# GALX4-0047N_PCB-1109N_REV-A_io_1.net
KiCad netlist of a schematic drawn in Altium Designer
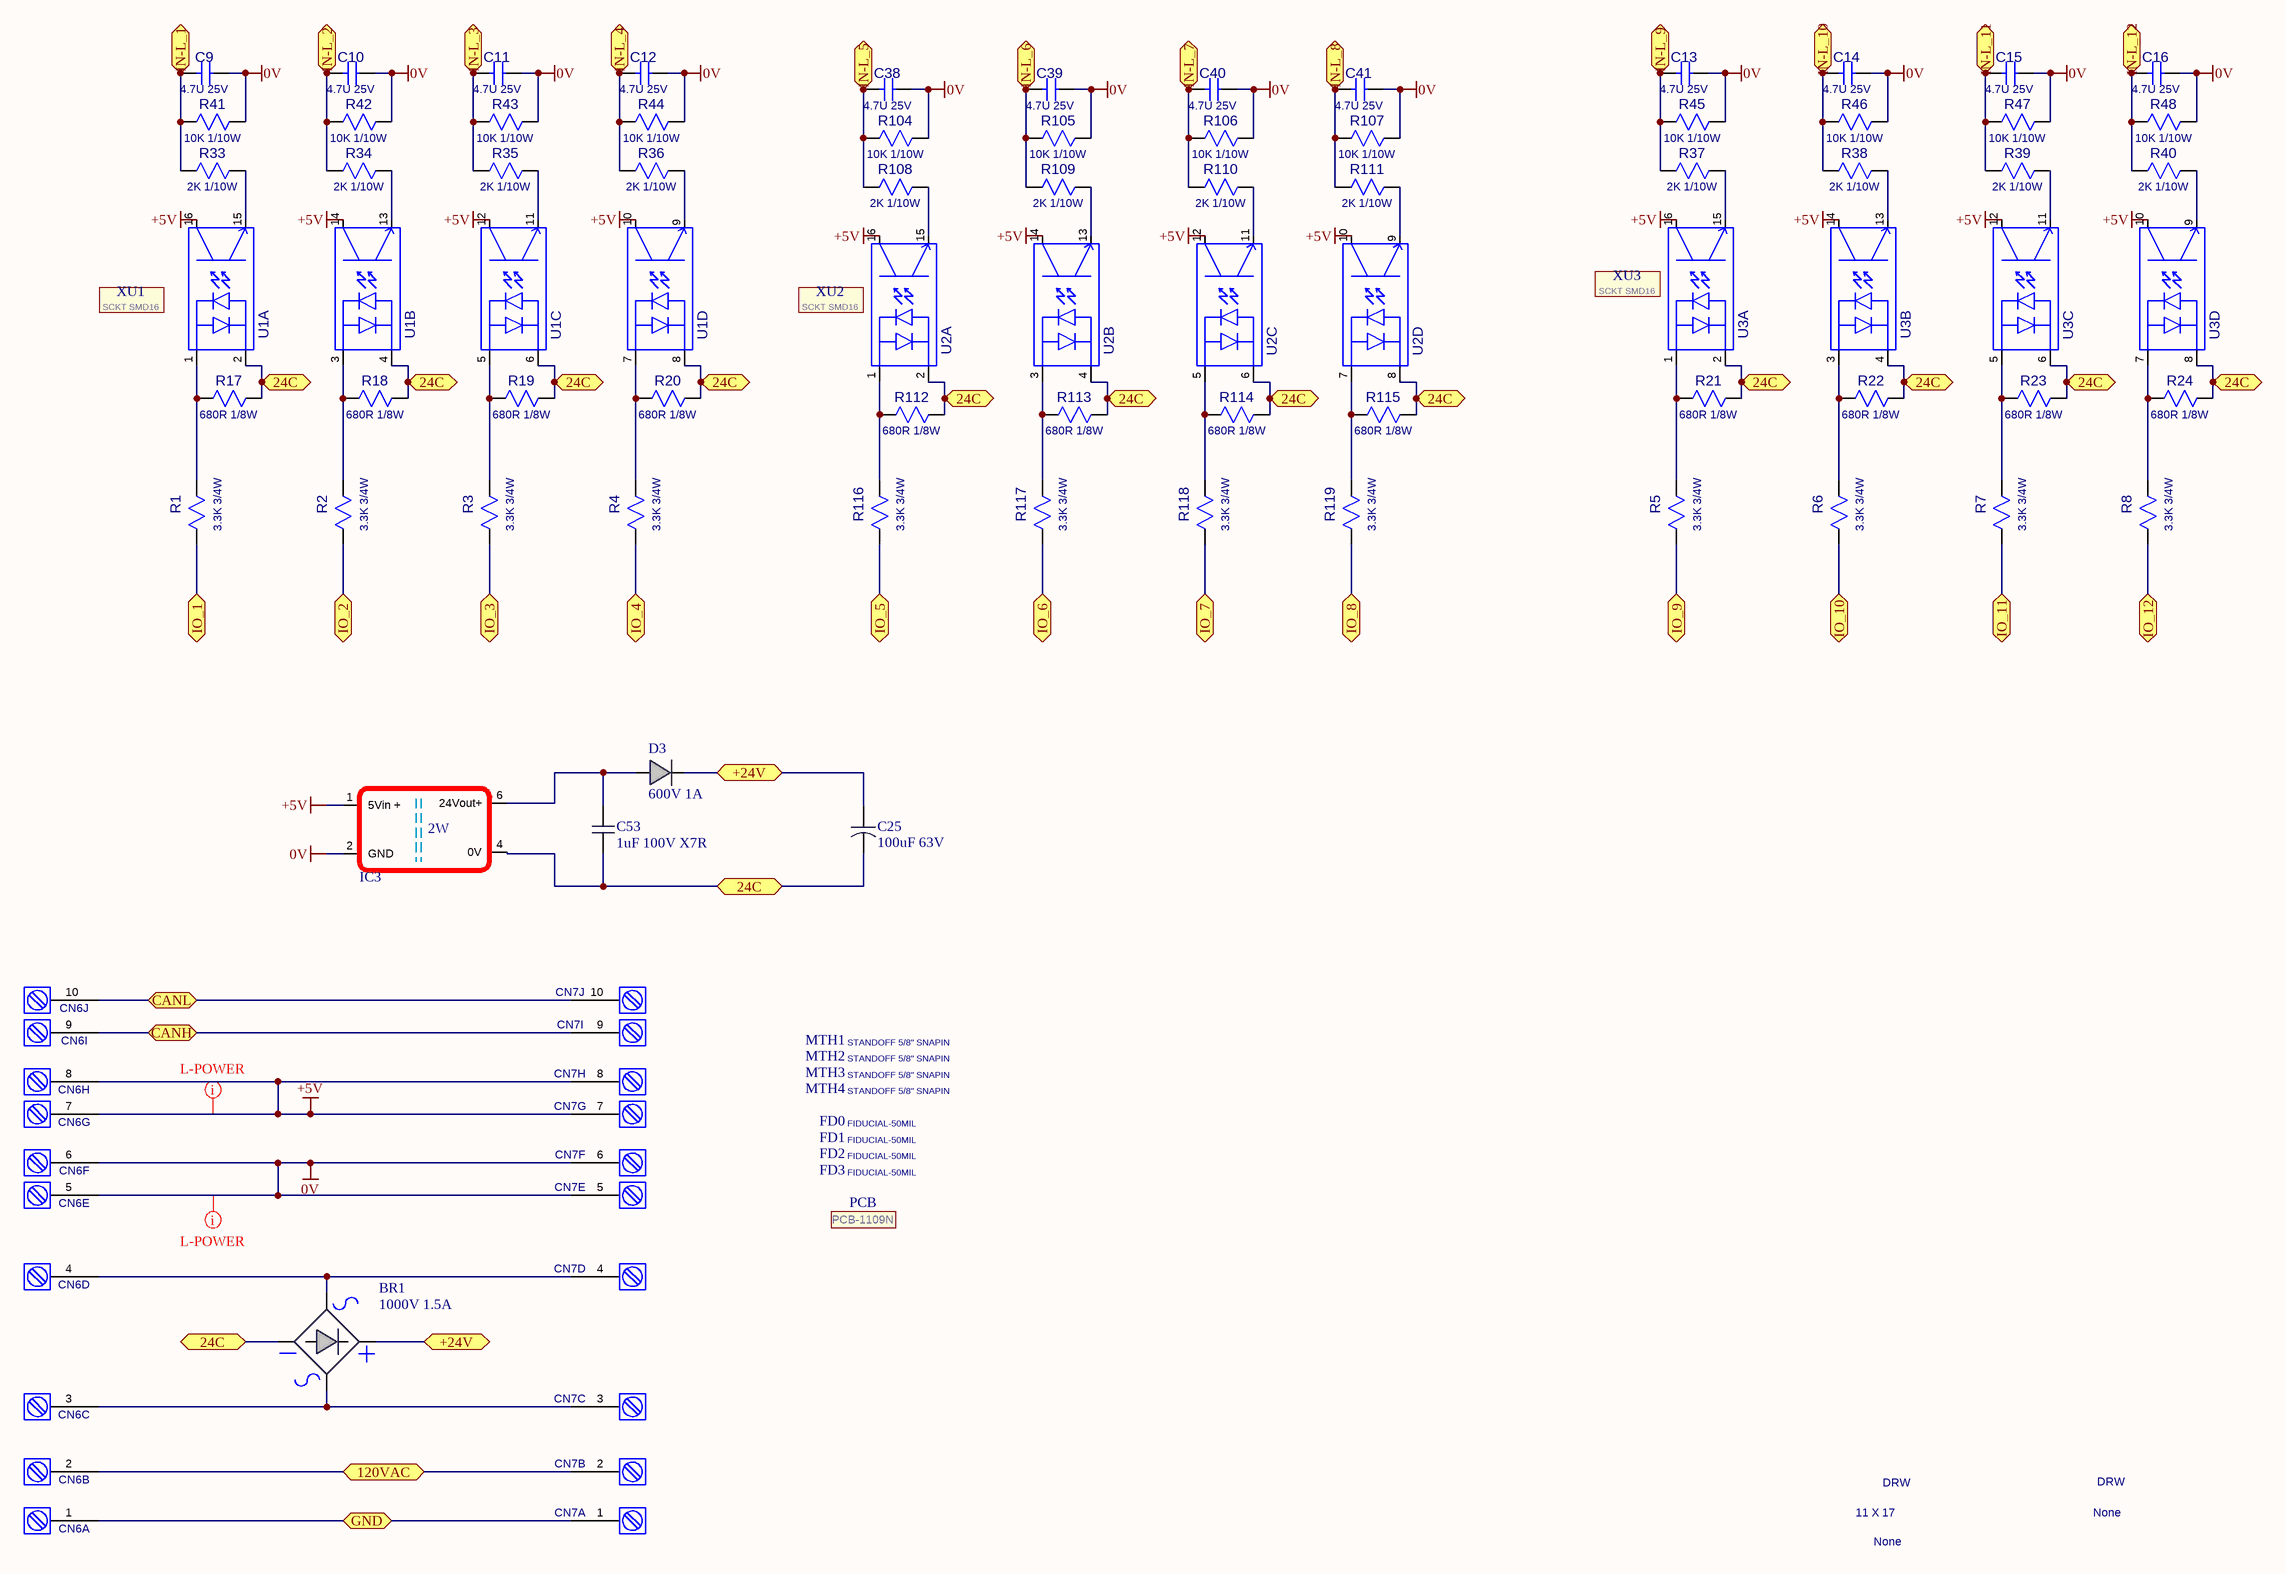
[diagram p0: GALX4-0047N_PCB-1109N_REV-A_io_1.SchDoc]

(export (version "E")
  (design (tool "Eeschema 10.0.6"))
  (components
    (comp (ref "BR1")
      (value "1000V 1.5A")
      (footprint "SDIP4")
      (description "DIODE,RECT BRIDGE 1000V 1.5A 4SDIP SMT")
      (fields (field (name "MANUFACTURER") "FAIRCHILD"))
      (libsource (lib "My Local Library") (part "DIOD-0081N"))
    )
    (comp (ref "C9")
      (value "4.7U 25V")
      (footprint "0805")
      (description "C-0805-D-4.7U-25V-10%")
      (fields (field (name "MANUFACTURER") "MURATA") (field (name "Comment") "CAP-0098N"))
      (libsource (lib "CAPACITOR") (part "CAP-0098N"))
    )
    (comp (ref "C10")
      (value "4.7U 25V")
      (footprint "0805")
      (description "C-0805-D-4.7U-25V-10%")
      (fields (field (name "MANUFACTURER") "MURATA") (field (name "Comment") "CAP-0098N"))
      (libsource (lib "CAPACITOR") (part "CAP-0098N"))
    )
    (comp (ref "C11")
      (value "4.7U 25V")
      (footprint "0805")
      (description "C-0805-D-4.7U-25V-10%")
      (fields (field (name "MANUFACTURER") "MURATA") (field (name "Comment") "CAP-0098N"))
      (libsource (lib "CAPACITOR") (part "CAP-0098N"))
    )
    (comp (ref "C12")
      (value "4.7U 25V")
      (footprint "0805")
      (description "C-0805-D-4.7U-25V-10%")
      (fields (field (name "MANUFACTURER") "MURATA") (field (name "Comment") "CAP-0098N"))
      (libsource (lib "CAPACITOR") (part "CAP-0098N"))
    )
    (comp (ref "C13")
      (value "4.7U 25V")
      (footprint "0805")
      (description "C-0805-D-4.7U-25V-10%")
      (fields (field (name "MANUFACTURER") "MURATA") (field (name "Comment") "CAP-0098N"))
      (libsource (lib "CAPACITOR") (part "CAP-0098N"))
    )
    (comp (ref "C14")
      (value "4.7U 25V")
      (footprint "0805")
      (description "C-0805-D-4.7U-25V-10%")
      (fields (field (name "MANUFACTURER") "MURATA") (field (name "Comment") "CAP-0098N"))
      (libsource (lib "CAPACITOR") (part "CAP-0098N"))
    )
    (comp (ref "C15")
      (value "4.7U 25V")
      (footprint "0805")
      (description "C-0805-D-4.7U-25V-10%")
      (fields (field (name "MANUFACTURER") "MURATA") (field (name "Comment") "CAP-0098N"))
      (libsource (lib "CAPACITOR") (part "CAP-0098N"))
    )
    (comp (ref "C16")
      (value "4.7U 25V")
      (footprint "0805")
      (description "C-0805-D-4.7U-25V-10%")
      (fields (field (name "MANUFACTURER") "MURATA") (field (name "Comment") "CAP-0098N"))
      (libsource (lib "CAPACITOR") (part "CAP-0098N"))
    )
    (comp (ref "C25")
      (value "100uF 63V")
      (footprint "D10.3")
      (description "CAP, 100UF 63V ELECT 20% 10.3MM SMT")
      (fields (field (name "MANUFACTURER") "UNITED CHEMICON"))
      (libsource (lib "My Local Library") (part "CAP-0104N"))
    )
    (comp (ref "C38")
      (value "4.7U 25V")
      (footprint "0805")
      (description "C-0805-D-4.7U-25V-10%")
      (fields (field (name "MANUFACTURER") "MURATA") (field (name "Comment") "CAP-0098N"))
      (libsource (lib "CAPACITOR") (part "CAP-0098N"))
    )
    (comp (ref "C39")
      (value "4.7U 25V")
      (footprint "0805")
      (description "C-0805-D-4.7U-25V-10%")
      (fields (field (name "MANUFACTURER") "MURATA") (field (name "Comment") "CAP-0098N"))
      (libsource (lib "CAPACITOR") (part "CAP-0098N"))
    )
    (comp (ref "C40")
      (value "4.7U 25V")
      (footprint "0805")
      (description "C-0805-D-4.7U-25V-10%")
      (fields (field (name "MANUFACTURER") "MURATA") (field (name "Comment") "CAP-0098N"))
      (libsource (lib "CAPACITOR") (part "CAP-0098N"))
    )
    (comp (ref "C41")
      (value "4.7U 25V")
      (footprint "0805")
      (description "C-0805-D-4.7U-25V-10%")
      (fields (field (name "MANUFACTURER") "MURATA") (field (name "Comment") "CAP-0098N"))
      (libsource (lib "CAPACITOR") (part "CAP-0098N"))
    )
    (comp (ref "C53")
      (value "1uF 100V X7R")
      (footprint "1206 - CAP")
      (description "CAP, 1UF 100V 10% X7R CERM 1206 SMT")
      (fields (field (name "MANUFACTURER") "MURATA"))
      (libsource (lib "My Local Library") (part "CAP-0110N"))
    )
    (comp (ref "CN6")
      (value "CONN-0193N")
      (footprint "CN_150_10P_VERT")
      (description "CN_150_10P_VERT")
      (fields (field (name "MANUFACTURER") "PHOENIX"))
      (libsource (lib "") (part "CONN-0193N_1"))
    )
    (comp (ref "CN7")
      (value "CONN-0193N")
      (footprint "CN_150_10P_VERT")
      (description "CN_150_10P_VERT")
      (fields (field (name "MANUFACTURER") "PHOENIX"))
      (libsource (lib "") (part "CONN-0193N_4"))
    )
    (comp (ref "D3")
      (value "600V 1A")
      (footprint "SMA")
      (description "DIODE,FAST 600V 1A SMA SMT")
      (fields (field (name "MANUFACTURER") "STMICRO"))
      (libsource (lib "My Local Library") (part "DIOD-0077N"))
    )
    (comp (ref "FD0")
      (value "FIDUCIAL-50MIL")
      (footprint "FIDUCIAL-50MIL")
      (libsource (lib "MISC") (part "FIDUCIAL-50MIL"))
    )
    (comp (ref "FD1")
      (value "FIDUCIAL-50MIL")
      (footprint "FIDUCIAL-50MIL")
      (libsource (lib "MISC") (part "FIDUCIAL-50MIL"))
    )
    (comp (ref "FD2")
      (value "FIDUCIAL-50MIL")
      (footprint "FIDUCIAL-50MIL")
      (libsource (lib "MISC") (part "FIDUCIAL-50MIL"))
    )
    (comp (ref "FD3")
      (value "FIDUCIAL-50MIL")
      (footprint "FIDUCIAL-50MIL")
      (libsource (lib "MISC") (part "FIDUCIAL-50MIL"))
    )
    (comp (ref "IC3")
      (value "PDM2-S5-S24-S")
      (footprint "PDM2-S5-S24-S")
      (description "CONV DC/DC 2W  5 --> 24V OUT SIP4")
      (fields (field (name "MANUFACTURER") "CUI INC"))
      (libsource (lib "My Local Library") (part "IC-PDM2-S5-S24-S"))
    )
    (comp (ref "MTH1")
      (value "STANDOFF 5/8\" SNAPIN")
      (footprint "STANDOFF-8-5/8\"")
      (description "STANDOFF-5/8-SNAP")
      (fields (field (name "MANUFACTURER") "KEYSTONE") (field (name "Comment") "HWPC-0018N"))
      (libsource (lib "MISC") (part "HWPC-0018N"))
    )
    (comp (ref "MTH2")
      (value "STANDOFF 5/8\" SNAPIN")
      (footprint "STANDOFF-8-5/8\"")
      (description "STANDOFF-5/8-SNAP")
      (fields (field (name "MANUFACTURER") "KEYSTONE") (field (name "Comment") "HWPC-0018N"))
      (libsource (lib "MISC") (part "HWPC-0018N"))
    )
    (comp (ref "MTH3")
      (value "STANDOFF 5/8\" SNAPIN")
      (footprint "STANDOFF-8-5/8\"")
      (description "STANDOFF-5/8-SNAP")
      (fields (field (name "MANUFACTURER") "KEYSTONE") (field (name "Comment") "HWPC-0018N"))
      (libsource (lib "MISC") (part "HWPC-0018N"))
    )
    (comp (ref "MTH4")
      (value "STANDOFF 5/8\" SNAPIN")
      (footprint "STANDOFF-8-5/8\"")
      (description "STANDOFF-5/8-SNAP")
      (fields (field (name "MANUFACTURER") "KEYSTONE") (field (name "Comment") "HWPC-0018N"))
      (libsource (lib "MISC") (part "HWPC-0018N"))
    )
    (comp (ref "PCB")
      (value "PCB")
      (description "PCB-0205N")
      (fields (field (name "MANUFACTURER") "CIRCUIT ENG") (field (name "GAL P/N") "PCB-1109N"))
      (libsource (lib "MISC") (part "PCB"))
    )
    (comp (ref "R1")
      (value "3.3K 3/4W")
      (footprint "2010")
      (description "R-2010-B-3.3K-3/4-5%")
      (fields (field (name "MANUFACTURER") "KOA SPEER") (field (name "Comment") "RES-0348N"))
      (libsource (lib "RESISTOR") (part "RES-0348N"))
    )
    (comp (ref "R2")
      (value "3.3K 3/4W")
      (footprint "2010")
      (description "R-2010-B-3.3K-3/4-5%")
      (fields (field (name "MANUFACTURER") "KOA SPEER") (field (name "Comment") "RES-0348N"))
      (libsource (lib "RESISTOR") (part "RES-0348N"))
    )
    (comp (ref "R3")
      (value "3.3K 3/4W")
      (footprint "2010")
      (description "R-2010-B-3.3K-3/4-5%")
      (fields (field (name "MANUFACTURER") "KOA SPEER") (field (name "Comment") "RES-0348N"))
      (libsource (lib "RESISTOR") (part "RES-0348N"))
    )
    (comp (ref "R4")
      (value "3.3K 3/4W")
      (footprint "2010")
      (description "R-2010-B-3.3K-3/4-5%")
      (fields (field (name "MANUFACTURER") "KOA SPEER") (field (name "Comment") "RES-0348N"))
      (libsource (lib "RESISTOR") (part "RES-0348N"))
    )
    (comp (ref "R5")
      (value "3.3K 3/4W")
      (footprint "2010")
      (description "R-2010-B-3.3K-3/4-5%")
      (fields (field (name "MANUFACTURER") "KOA SPEER") (field (name "Comment") "RES-0348N"))
      (libsource (lib "RESISTOR") (part "RES-0348N"))
    )
    (comp (ref "R6")
      (value "3.3K 3/4W")
      (footprint "2010")
      (description "R-2010-B-3.3K-3/4-5%")
      (fields (field (name "MANUFACTURER") "KOA SPEER") (field (name "Comment") "RES-0348N"))
      (libsource (lib "RESISTOR") (part "RES-0348N"))
    )
    (comp (ref "R7")
      (value "3.3K 3/4W")
      (footprint "2010")
      (description "R-2010-B-3.3K-3/4-5%")
      (fields (field (name "MANUFACTURER") "KOA SPEER") (field (name "Comment") "RES-0348N"))
      (libsource (lib "RESISTOR") (part "RES-0348N"))
    )
    (comp (ref "R8")
      (value "3.3K 3/4W")
      (footprint "2010")
      (description "R-2010-B-3.3K-3/4-5%")
      (fields (field (name "MANUFACTURER") "KOA SPEER") (field (name "Comment") "RES-0348N"))
      (libsource (lib "RESISTOR") (part "RES-0348N"))
    )
    (comp (ref "R17")
      (value "680R 1/8W")
      (footprint "0805")
      (description "R-0805-A-680R-1/8-5%")
      (fields (field (name "MANUFACTURER") "YAGEO") (field (name "Comment") "RES-0338N"))
      (libsource (lib "RESISTOR") (part "RES-0338N"))
    )
    (comp (ref "R18")
      (value "680R 1/8W")
      (footprint "0805")
      (description "R-0805-A-680R-1/8-5%")
      (fields (field (name "MANUFACTURER") "YAGEO") (field (name "Comment") "RES-0338N"))
      (libsource (lib "RESISTOR") (part "RES-0338N"))
    )
    (comp (ref "R19")
      (value "680R 1/8W")
      (footprint "0805")
      (description "R-0805-A-680R-1/8-5%")
      (fields (field (name "MANUFACTURER") "YAGEO") (field (name "Comment") "RES-0338N"))
      (libsource (lib "RESISTOR") (part "RES-0338N"))
    )
    (comp (ref "R20")
      (value "680R 1/8W")
      (footprint "0805")
      (description "R-0805-A-680R-1/8-5%")
      (fields (field (name "MANUFACTURER") "YAGEO") (field (name "Comment") "RES-0338N"))
      (libsource (lib "RESISTOR") (part "RES-0338N"))
    )
    (comp (ref "R21")
      (value "680R 1/8W")
      (footprint "0805")
      (description "R-0805-A-680R-1/8-5%")
      (fields (field (name "MANUFACTURER") "YAGEO") (field (name "Comment") "RES-0338N"))
      (libsource (lib "RESISTOR") (part "RES-0338N"))
    )
    (comp (ref "R22")
      (value "680R 1/8W")
      (footprint "0805")
      (description "R-0805-A-680R-1/8-5%")
      (fields (field (name "MANUFACTURER") "YAGEO") (field (name "Comment") "RES-0338N"))
      (libsource (lib "RESISTOR") (part "RES-0338N"))
    )
    (comp (ref "R23")
      (value "680R 1/8W")
      (footprint "0805")
      (description "R-0805-A-680R-1/8-5%")
      (fields (field (name "MANUFACTURER") "YAGEO") (field (name "Comment") "RES-0338N"))
      (libsource (lib "RESISTOR") (part "RES-0338N"))
    )
    (comp (ref "R24")
      (value "680R 1/8W")
      (footprint "0805")
      (description "R-0805-A-680R-1/8-5%")
      (fields (field (name "MANUFACTURER") "YAGEO") (field (name "Comment") "RES-0338N"))
      (libsource (lib "RESISTOR") (part "RES-0338N"))
    )
    (comp (ref "R33")
      (value "2K 1/10W")
      (footprint "0603")
      (description "R-0603-B-2.0K-1/10-5%")
      (fields (field (name "MANUFACTURER") "PANASONIC-ECG") (field (name "Comment") "RES-0315N"))
      (libsource (lib "RESISTOR") (part "RES-0315N"))
    )
    (comp (ref "R34")
      (value "2K 1/10W")
      (footprint "0603")
      (description "R-0603-B-2.0K-1/10-5%")
      (fields (field (name "MANUFACTURER") "PANASONIC-ECG") (field (name "Comment") "RES-0315N"))
      (libsource (lib "RESISTOR") (part "RES-0315N"))
    )
    (comp (ref "R35")
      (value "2K 1/10W")
      (footprint "0603")
      (description "R-0603-B-2.0K-1/10-5%")
      (fields (field (name "MANUFACTURER") "PANASONIC-ECG") (field (name "Comment") "RES-0315N"))
      (libsource (lib "RESISTOR") (part "RES-0315N"))
    )
    (comp (ref "R36")
      (value "2K 1/10W")
      (footprint "0603")
      (description "R-0603-B-2.0K-1/10-5%")
      (fields (field (name "MANUFACTURER") "PANASONIC-ECG") (field (name "Comment") "RES-0315N"))
      (libsource (lib "RESISTOR") (part "RES-0315N"))
    )
    (comp (ref "R37")
      (value "2K 1/10W")
      (footprint "0603")
      (description "R-0603-B-2.0K-1/10-5%")
      (fields (field (name "MANUFACTURER") "PANASONIC-ECG") (field (name "Comment") "RES-0315N"))
      (libsource (lib "RESISTOR") (part "RES-0315N"))
    )
    (comp (ref "R38")
      (value "2K 1/10W")
      (footprint "0603")
      (description "R-0603-B-2.0K-1/10-5%")
      (fields (field (name "MANUFACTURER") "PANASONIC-ECG") (field (name "Comment") "RES-0315N"))
      (libsource (lib "RESISTOR") (part "RES-0315N"))
    )
    (comp (ref "R39")
      (value "2K 1/10W")
      (footprint "0603")
      (description "R-0603-B-2.0K-1/10-5%")
      (fields (field (name "MANUFACTURER") "PANASONIC-ECG") (field (name "Comment") "RES-0315N"))
      (libsource (lib "RESISTOR") (part "RES-0315N"))
    )
    (comp (ref "R40")
      (value "2K 1/10W")
      (footprint "0603")
      (description "R-0603-B-2.0K-1/10-5%")
      (fields (field (name "MANUFACTURER") "PANASONIC-ECG") (field (name "Comment") "RES-0315N"))
      (libsource (lib "RESISTOR") (part "RES-0315N"))
    )
    (comp (ref "R41")
      (value "10K 1/10W")
      (footprint "0603")
      (description "R-0603-B-10.0K-1/10-5%")
      (fields (field (name "MANUFACTURER") "PANASONIC-ECG") (field (name "Comment") "RES-0314N"))
      (libsource (lib "RESISTOR") (part "RES-0314N"))
    )
    (comp (ref "R42")
      (value "10K 1/10W")
      (footprint "0603")
      (description "R-0603-B-10.0K-1/10-5%")
      (fields (field (name "MANUFACTURER") "PANASONIC-ECG") (field (name "Comment") "RES-0314N"))
      (libsource (lib "RESISTOR") (part "RES-0314N"))
    )
    (comp (ref "R43")
      (value "10K 1/10W")
      (footprint "0603")
      (description "R-0603-B-10.0K-1/10-5%")
      (fields (field (name "MANUFACTURER") "PANASONIC-ECG") (field (name "Comment") "RES-0314N"))
      (libsource (lib "RESISTOR") (part "RES-0314N"))
    )
    (comp (ref "R44")
      (value "10K 1/10W")
      (footprint "0603")
      (description "R-0603-B-10.0K-1/10-5%")
      (fields (field (name "MANUFACTURER") "PANASONIC-ECG") (field (name "Comment") "RES-0314N"))
      (libsource (lib "RESISTOR") (part "RES-0314N"))
    )
    (comp (ref "R45")
      (value "10K 1/10W")
      (footprint "0603")
      (description "R-0603-B-10.0K-1/10-5%")
      (fields (field (name "MANUFACTURER") "PANASONIC-ECG") (field (name "Comment") "RES-0314N"))
      (libsource (lib "RESISTOR") (part "RES-0314N"))
    )
    (comp (ref "R46")
      (value "10K 1/10W")
      (footprint "0603")
      (description "R-0603-B-10.0K-1/10-5%")
      (fields (field (name "MANUFACTURER") "PANASONIC-ECG") (field (name "Comment") "RES-0314N"))
      (libsource (lib "RESISTOR") (part "RES-0314N"))
    )
    (comp (ref "R47")
      (value "10K 1/10W")
      (footprint "0603")
      (description "R-0603-B-10.0K-1/10-5%")
      (fields (field (name "MANUFACTURER") "PANASONIC-ECG") (field (name "Comment") "RES-0314N"))
      (libsource (lib "RESISTOR") (part "RES-0314N"))
    )
    (comp (ref "R48")
      (value "10K 1/10W")
      (footprint "0603")
      (description "R-0603-B-10.0K-1/10-5%")
      (fields (field (name "MANUFACTURER") "PANASONIC-ECG") (field (name "Comment") "RES-0314N"))
      (libsource (lib "RESISTOR") (part "RES-0314N"))
    )
    (comp (ref "R104")
      (value "10K 1/10W")
      (footprint "0603")
      (description "R-0603-B-10.0K-1/10-5%")
      (fields (field (name "MANUFACTURER") "PANASONIC-ECG") (field (name "Comment") "RES-0314N"))
      (libsource (lib "RESISTOR") (part "RES-0314N"))
    )
    (comp (ref "R105")
      (value "10K 1/10W")
      (footprint "0603")
      (description "R-0603-B-10.0K-1/10-5%")
      (fields (field (name "MANUFACTURER") "PANASONIC-ECG") (field (name "Comment") "RES-0314N"))
      (libsource (lib "RESISTOR") (part "RES-0314N"))
    )
    (comp (ref "R106")
      (value "10K 1/10W")
      (footprint "0603")
      (description "R-0603-B-10.0K-1/10-5%")
      (fields (field (name "MANUFACTURER") "PANASONIC-ECG") (field (name "Comment") "RES-0314N"))
      (libsource (lib "RESISTOR") (part "RES-0314N"))
    )
    (comp (ref "R107")
      (value "10K 1/10W")
      (footprint "0603")
      (description "R-0603-B-10.0K-1/10-5%")
      (fields (field (name "MANUFACTURER") "PANASONIC-ECG") (field (name "Comment") "RES-0314N"))
      (libsource (lib "RESISTOR") (part "RES-0314N"))
    )
    (comp (ref "R108")
      (value "2K 1/10W")
      (footprint "0603")
      (description "R-0603-B-2.0K-1/10-5%")
      (fields (field (name "MANUFACTURER") "PANASONIC-ECG") (field (name "Comment") "RES-0315N"))
      (libsource (lib "RESISTOR") (part "RES-0315N"))
    )
    (comp (ref "R109")
      (value "2K 1/10W")
      (footprint "0603")
      (description "R-0603-B-2.0K-1/10-5%")
      (fields (field (name "MANUFACTURER") "PANASONIC-ECG") (field (name "Comment") "RES-0315N"))
      (libsource (lib "RESISTOR") (part "RES-0315N"))
    )
    (comp (ref "R110")
      (value "2K 1/10W")
      (footprint "0603")
      (description "R-0603-B-2.0K-1/10-5%")
      (fields (field (name "MANUFACTURER") "PANASONIC-ECG") (field (name "Comment") "RES-0315N"))
      (libsource (lib "RESISTOR") (part "RES-0315N"))
    )
    (comp (ref "R111")
      (value "2K 1/10W")
      (footprint "0603")
      (description "R-0603-B-2.0K-1/10-5%")
      (fields (field (name "MANUFACTURER") "PANASONIC-ECG") (field (name "Comment") "RES-0315N"))
      (libsource (lib "RESISTOR") (part "RES-0315N"))
    )
    (comp (ref "R112")
      (value "680R 1/8W")
      (footprint "0805")
      (description "R-0805-A-680R-1/8-5%")
      (fields (field (name "MANUFACTURER") "YAGEO") (field (name "Comment") "RES-0338N"))
      (libsource (lib "RESISTOR") (part "RES-0338N"))
    )
    (comp (ref "R113")
      (value "680R 1/8W")
      (footprint "0805")
      (description "R-0805-A-680R-1/8-5%")
      (fields (field (name "MANUFACTURER") "YAGEO") (field (name "Comment") "RES-0338N"))
      (libsource (lib "RESISTOR") (part "RES-0338N"))
    )
    (comp (ref "R114")
      (value "680R 1/8W")
      (footprint "0805")
      (description "R-0805-A-680R-1/8-5%")
      (fields (field (name "MANUFACTURER") "YAGEO") (field (name "Comment") "RES-0338N"))
      (libsource (lib "RESISTOR") (part "RES-0338N"))
    )
    (comp (ref "R115")
      (value "680R 1/8W")
      (footprint "0805")
      (description "R-0805-A-680R-1/8-5%")
      (fields (field (name "MANUFACTURER") "YAGEO") (field (name "Comment") "RES-0338N"))
      (libsource (lib "RESISTOR") (part "RES-0338N"))
    )
    (comp (ref "R116")
      (value "3.3K 3/4W")
      (footprint "2010")
      (description "R-2010-B-3.3K-3/4-5%")
      (fields (field (name "MANUFACTURER") "KOA SPEER") (field (name "Comment") "RES-0348N"))
      (libsource (lib "RESISTOR") (part "RES-0348N"))
    )
    (comp (ref "R117")
      (value "3.3K 3/4W")
      (footprint "2010")
      (description "R-2010-B-3.3K-3/4-5%")
      (fields (field (name "MANUFACTURER") "KOA SPEER") (field (name "Comment") "RES-0348N"))
      (libsource (lib "RESISTOR") (part "RES-0348N"))
    )
    (comp (ref "R118")
      (value "3.3K 3/4W")
      (footprint "2010")
      (description "R-2010-B-3.3K-3/4-5%")
      (fields (field (name "MANUFACTURER") "KOA SPEER") (field (name "Comment") "RES-0348N"))
      (libsource (lib "RESISTOR") (part "RES-0348N"))
    )
    (comp (ref "R119")
      (value "3.3K 3/4W")
      (footprint "2010")
      (description "R-2010-B-3.3K-3/4-5%")
      (fields (field (name "MANUFACTURER") "KOA SPEER") (field (name "Comment") "RES-0348N"))
      (libsource (lib "RESISTOR") (part "RES-0348N"))
    )
    (comp (ref "U1")
      (value "IC-0068N")
      (footprint "DIP16FORSMD")
      (description "LTV-844-DIP16")
      (fields (field (name "MANUFACTURER") "LITE-ON"))
      (libsource (lib "IC") (part "IC-0068N"))
    )
    (comp (ref "U2")
      (value "IC-0068N")
      (footprint "DIP16FORSMD")
      (description "LTV-844-DIP16")
      (fields (field (name "MANUFACTURER") "LITE-ON"))
      (libsource (lib "IC") (part "IC-0068N"))
    )
    (comp (ref "U3")
      (value "IC-0068N")
      (footprint "DIP16FORSMD")
      (description "LTV-844-DIP16")
      (fields (field (name "MANUFACTURER") "LITE-ON"))
      (libsource (lib "IC") (part "IC-0068N"))
    )
    (comp (ref "XU1")
      (value "SCKT SMD16")
      (footprint "SCKT-SMD16")
      (description "SOCKET_SMD16")
      (fields (field (name "MANUFACTURER") "MILL-MAX") (field (name "Comment") "SCKT-0029N"))
      (libsource (lib "IC") (part "SCKT-0029N"))
    )
    (comp (ref "XU2")
      (value "SCKT SMD16")
      (footprint "SCKT-SMD16")
      (description "SOCKET_SMD16")
      (fields (field (name "MANUFACTURER") "MILL-MAX") (field (name "Comment") "SCKT-0029N"))
      (libsource (lib "IC") (part "SCKT-0029N"))
    )
    (comp (ref "XU3")
      (value "SCKT SMD16")
      (footprint "SCKT-SMD16")
      (description "SOCKET_SMD16")
      (fields (field (name "MANUFACTURER") "MILL-MAX") (field (name "Comment") "SCKT-0029N"))
      (libsource (lib "IC") (part "SCKT-0029N"))
    )
  )
  (nets
    (net (code "1") (name "+5V") (class "Default")
      (node (ref "CN6") (pin "7") (pintype "passive"))
      (node (ref "CN6") (pin "8") (pintype "passive"))
      (node (ref "CN7") (pin "7") (pintype "passive"))
      (node (ref "CN7") (pin "8") (pintype "passive"))
      (node (ref "IC3") (pin "1") (pinfunction "5Vin_+_1") (pintype "power_in"))
      (node (ref "U1") (pin "10") (pintype "passive"))
      (node (ref "U1") (pin "12") (pintype "passive"))
      (node (ref "U1") (pin "14") (pintype "passive"))
      (node (ref "U1") (pin "16") (pintype "passive"))
      (node (ref "U2") (pin "10") (pintype "passive"))
      (node (ref "U2") (pin "12") (pintype "passive"))
      (node (ref "U2") (pin "14") (pintype "passive"))
      (node (ref "U2") (pin "16") (pintype "passive"))
      (node (ref "U3") (pin "10") (pintype "passive"))
      (node (ref "U3") (pin "12") (pintype "passive"))
      (node (ref "U3") (pin "14") (pintype "passive"))
      (node (ref "U3") (pin "16") (pintype "passive"))
    )
    (net (code "2") (name "/+24V") (class "Default")
      (node (ref "BR1") (pin "1") (pinfunction "+_1") (pintype "passive"))
      (node (ref "C25") (pin "1") (pintype "passive"))
      (node (ref "D3") (pin "2") (pintype "passive"))
    )
    (net (code "3") (name "/24C") (class "Default")
      (node (ref "BR1") (pin "2") (pinfunction "-_2") (pintype "passive"))
      (node (ref "C25") (pin "2") (pintype "passive"))
      (node (ref "C53") (pin "1") (pinfunction "A_1") (pintype "passive"))
      (node (ref "IC3") (pin "4") (pinfunction "0V_4") (pintype "power_in"))
      (node (ref "R112") (pin "2") (pintype "passive"))
      (node (ref "R113") (pin "2") (pintype "passive"))
      (node (ref "R114") (pin "2") (pintype "passive"))
      (node (ref "R115") (pin "2") (pintype "passive"))
      (node (ref "R17") (pin "2") (pintype "passive"))
      (node (ref "R18") (pin "2") (pintype "passive"))
      (node (ref "R19") (pin "2") (pintype "passive"))
      (node (ref "R20") (pin "2") (pintype "passive"))
      (node (ref "R21") (pin "2") (pintype "passive"))
      (node (ref "R22") (pin "2") (pintype "passive"))
      (node (ref "R23") (pin "2") (pintype "passive"))
      (node (ref "R24") (pin "2") (pintype "passive"))
      (node (ref "U1") (pin "2") (pintype "passive"))
      (node (ref "U1") (pin "4") (pintype "passive"))
      (node (ref "U1") (pin "6") (pintype "passive"))
      (node (ref "U1") (pin "8") (pintype "passive"))
      (node (ref "U2") (pin "2") (pintype "passive"))
      (node (ref "U2") (pin "4") (pintype "passive"))
      (node (ref "U2") (pin "6") (pintype "passive"))
      (node (ref "U2") (pin "8") (pintype "passive"))
      (node (ref "U3") (pin "2") (pintype "passive"))
      (node (ref "U3") (pin "4") (pintype "passive"))
      (node (ref "U3") (pin "6") (pintype "passive"))
      (node (ref "U3") (pin "8") (pintype "passive"))
    )
    (net (code "4") (name "/120VAC") (class "Default")
      (node (ref "CN6") (pin "2") (pintype "passive"))
      (node (ref "CN7") (pin "2") (pintype "passive"))
    )
    (net (code "5") (name "/CANH") (class "Default")
      (node (ref "CN6") (pin "9") (pintype "passive"))
      (node (ref "CN7") (pin "9") (pintype "passive"))
    )
    (net (code "6") (name "/CANL") (class "Default")
      (node (ref "CN6") (pin "10") (pintype "passive"))
      (node (ref "CN7") (pin "10") (pintype "passive"))
    )
    (net (code "7") (name "/GND") (class "Default")
      (node (ref "CN6") (pin "1") (pintype "passive"))
      (node (ref "CN7") (pin "1") (pintype "passive"))
    )
    (net (code "8") (name "/IN-L_1") (class "Default")
      (node (ref "C9") (pin "1") (pinfunction "A_1") (pintype "passive"))
      (node (ref "R33") (pin "1") (pintype "passive"))
      (node (ref "R41") (pin "1") (pintype "passive"))
    )
    (net (code "9") (name "/IN-L_2") (class "Default")
      (node (ref "C10") (pin "1") (pinfunction "A_1") (pintype "passive"))
      (node (ref "R34") (pin "1") (pintype "passive"))
      (node (ref "R42") (pin "1") (pintype "passive"))
    )
    (net (code "10") (name "/IN-L_3") (class "Default")
      (node (ref "C11") (pin "1") (pinfunction "A_1") (pintype "passive"))
      (node (ref "R35") (pin "1") (pintype "passive"))
      (node (ref "R43") (pin "1") (pintype "passive"))
    )
    (net (code "11") (name "/IN-L_4") (class "Default")
      (node (ref "C12") (pin "1") (pinfunction "A_1") (pintype "passive"))
      (node (ref "R36") (pin "1") (pintype "passive"))
      (node (ref "R44") (pin "1") (pintype "passive"))
    )
    (net (code "12") (name "/IN-L_5") (class "Default")
      (node (ref "C38") (pin "1") (pinfunction "A_1") (pintype "passive"))
      (node (ref "R104") (pin "1") (pintype "passive"))
      (node (ref "R108") (pin "1") (pintype "passive"))
    )
    (net (code "13") (name "/IN-L_6") (class "Default")
      (node (ref "C39") (pin "1") (pinfunction "A_1") (pintype "passive"))
      (node (ref "R105") (pin "1") (pintype "passive"))
      (node (ref "R109") (pin "1") (pintype "passive"))
    )
    (net (code "14") (name "/IN-L_7") (class "Default")
      (node (ref "C40") (pin "1") (pinfunction "A_1") (pintype "passive"))
      (node (ref "R106") (pin "1") (pintype "passive"))
      (node (ref "R110") (pin "1") (pintype "passive"))
    )
    (net (code "15") (name "/IN-L_8") (class "Default")
      (node (ref "C41") (pin "1") (pinfunction "A_1") (pintype "passive"))
      (node (ref "R107") (pin "1") (pintype "passive"))
      (node (ref "R111") (pin "1") (pintype "passive"))
    )
    (net (code "16") (name "/IN-L_9") (class "Default")
      (node (ref "C13") (pin "1") (pinfunction "A_1") (pintype "passive"))
      (node (ref "R37") (pin "1") (pintype "passive"))
      (node (ref "R45") (pin "1") (pintype "passive"))
    )
    (net (code "17") (name "/IN-L_10") (class "Default")
      (node (ref "C14") (pin "1") (pinfunction "A_1") (pintype "passive"))
      (node (ref "R38") (pin "1") (pintype "passive"))
      (node (ref "R46") (pin "1") (pintype "passive"))
    )
    (net (code "18") (name "/IN-L_11") (class "Default")
      (node (ref "C15") (pin "1") (pinfunction "A_1") (pintype "passive"))
      (node (ref "R39") (pin "1") (pintype "passive"))
      (node (ref "R47") (pin "1") (pintype "passive"))
    )
    (net (code "19") (name "/IN-L_12") (class "Default")
      (node (ref "C16") (pin "1") (pinfunction "A_1") (pintype "passive"))
      (node (ref "R40") (pin "1") (pintype "passive"))
      (node (ref "R48") (pin "1") (pintype "passive"))
    )
    (net (code "20") (name "/IO_1") (class "Default") (node (ref "R1") (pin "1") (pintype "passive")))
    (net (code "21") (name "/IO_2") (class "Default") (node (ref "R2") (pin "1") (pintype "passive")))
    (net (code "22") (name "/IO_3") (class "Default") (node (ref "R3") (pin "1") (pintype "passive")))
    (net (code "23") (name "/IO_4") (class "Default") (node (ref "R4") (pin "1") (pintype "passive")))
    (net (code "24") (name "/IO_5") (class "Default") (node (ref "R116") (pin "1") (pintype "passive")))
    (net (code "25") (name "/IO_6") (class "Default") (node (ref "R117") (pin "1") (pintype "passive")))
    (net (code "26") (name "/IO_7") (class "Default") (node (ref "R118") (pin "1") (pintype "passive")))
    (net (code "27") (name "/IO_8") (class "Default") (node (ref "R119") (pin "1") (pintype "passive")))
    (net (code "28") (name "/IO_9") (class "Default") (node (ref "R5") (pin "1") (pintype "passive")))
    (net (code "29") (name "/IO_10") (class "Default") (node (ref "R6") (pin "1") (pintype "passive")))
    (net (code "30") (name "/IO_11") (class "Default") (node (ref "R7") (pin "1") (pintype "passive")))
    (net (code "31") (name "/IO_12") (class "Default") (node (ref "R8") (pin "1") (pintype "passive")))
    (net (code "32") (name "0V") (class "Default")
      (node (ref "C10") (pin "2") (pinfunction "B_2") (pintype "passive"))
      (node (ref "C11") (pin "2") (pinfunction "B_2") (pintype "passive"))
      (node (ref "C12") (pin "2") (pinfunction "B_2") (pintype "passive"))
      (node (ref "C13") (pin "2") (pinfunction "B_2") (pintype "passive"))
      (node (ref "C14") (pin "2") (pinfunction "B_2") (pintype "passive"))
      (node (ref "C15") (pin "2") (pinfunction "B_2") (pintype "passive"))
      (node (ref "C16") (pin "2") (pinfunction "B_2") (pintype "passive"))
      (node (ref "C38") (pin "2") (pinfunction "B_2") (pintype "passive"))
      (node (ref "C39") (pin "2") (pinfunction "B_2") (pintype "passive"))
      (node (ref "C40") (pin "2") (pinfunction "B_2") (pintype "passive"))
      (node (ref "C41") (pin "2") (pinfunction "B_2") (pintype "passive"))
      (node (ref "C9") (pin "2") (pinfunction "B_2") (pintype "passive"))
      (node (ref "CN6") (pin "5") (pintype "passive"))
      (node (ref "CN6") (pin "6") (pintype "passive"))
      (node (ref "CN7") (pin "5") (pintype "passive"))
      (node (ref "CN7") (pin "6") (pintype "passive"))
      (node (ref "IC3") (pin "2") (pinfunction "GND_2") (pintype "power_in"))
      (node (ref "R104") (pin "2") (pintype "passive"))
      (node (ref "R105") (pin "2") (pintype "passive"))
      (node (ref "R106") (pin "2") (pintype "passive"))
      (node (ref "R107") (pin "2") (pintype "passive"))
      (node (ref "R41") (pin "2") (pintype "passive"))
      (node (ref "R42") (pin "2") (pintype "passive"))
      (node (ref "R43") (pin "2") (pintype "passive"))
      (node (ref "R44") (pin "2") (pintype "passive"))
      (node (ref "R45") (pin "2") (pintype "passive"))
      (node (ref "R46") (pin "2") (pintype "passive"))
      (node (ref "R47") (pin "2") (pintype "passive"))
      (node (ref "R48") (pin "2") (pintype "passive"))
    )
    (net (code "33") (name "Net-(BR1-AC_1)") (class "Default")
      (node (ref "BR1") (pin "3") (pinfunction "AC_1_3") (pintype "passive"))
      (node (ref "CN6") (pin "4") (pintype "passive"))
      (node (ref "CN7") (pin "4") (pintype "passive"))
    )
    (net (code "34") (name "Net-(BR1-AC_2)") (class "Default")
      (node (ref "BR1") (pin "4") (pinfunction "AC_2_4") (pintype "passive"))
      (node (ref "CN6") (pin "3") (pintype "passive"))
      (node (ref "CN7") (pin "3") (pintype "passive"))
    )
    (net (code "35") (name "Net-(C53-B)") (class "Default")
      (node (ref "C53") (pin "2") (pinfunction "B_2") (pintype "passive"))
      (node (ref "D3") (pin "1") (pintype "passive"))
      (node (ref "IC3") (pin "6") (pinfunction "24Vout+_6") (pintype "power_in"))
    )
    (net (code "36") (name "Net-(R1-Pad2)") (class "Default")
      (node (ref "R1") (pin "2") (pintype "passive"))
      (node (ref "R17") (pin "1") (pintype "passive"))
      (node (ref "U1") (pin "1") (pintype "passive"))
    )
    (net (code "37") (name "Net-(R18-Pad1)") (class "Default")
      (node (ref "R18") (pin "1") (pintype "passive"))
      (node (ref "R2") (pin "2") (pintype "passive"))
      (node (ref "U1") (pin "3") (pintype "passive"))
    )
    (net (code "38") (name "Net-(R19-Pad1)") (class "Default")
      (node (ref "R19") (pin "1") (pintype "passive"))
      (node (ref "R3") (pin "2") (pintype "passive"))
      (node (ref "U1") (pin "5") (pintype "passive"))
    )
    (net (code "39") (name "Net-(R20-Pad1)") (class "Default")
      (node (ref "R20") (pin "1") (pintype "passive"))
      (node (ref "R4") (pin "2") (pintype "passive"))
      (node (ref "U1") (pin "7") (pintype "passive"))
    )
    (net (code "40") (name "Net-(R21-Pad1)") (class "Default")
      (node (ref "R21") (pin "1") (pintype "passive"))
      (node (ref "R5") (pin "2") (pintype "passive"))
      (node (ref "U3") (pin "1") (pintype "passive"))
    )
    (net (code "41") (name "Net-(R22-Pad1)") (class "Default")
      (node (ref "R22") (pin "1") (pintype "passive"))
      (node (ref "R6") (pin "2") (pintype "passive"))
      (node (ref "U3") (pin "3") (pintype "passive"))
    )
    (net (code "42") (name "Net-(R23-Pad1)") (class "Default")
      (node (ref "R23") (pin "1") (pintype "passive"))
      (node (ref "R7") (pin "2") (pintype "passive"))
      (node (ref "U3") (pin "5") (pintype "passive"))
    )
    (net (code "43") (name "Net-(R24-Pad1)") (class "Default")
      (node (ref "R24") (pin "1") (pintype "passive"))
      (node (ref "R8") (pin "2") (pintype "passive"))
      (node (ref "U3") (pin "7") (pintype "passive"))
    )
    (net (code "44") (name "Net-(R33-Pad2)") (class "Default")
      (node (ref "R33") (pin "2") (pintype "passive"))
      (node (ref "U1") (pin "15") (pintype "passive"))
    )
    (net (code "45") (name "Net-(R34-Pad2)") (class "Default")
      (node (ref "R34") (pin "2") (pintype "passive"))
      (node (ref "U1") (pin "13") (pintype "passive"))
    )
    (net (code "46") (name "Net-(R35-Pad2)") (class "Default")
      (node (ref "R35") (pin "2") (pintype "passive"))
      (node (ref "U1") (pin "11") (pintype "passive"))
    )
    (net (code "47") (name "Net-(R36-Pad2)") (class "Default")
      (node (ref "R36") (pin "2") (pintype "passive"))
      (node (ref "U1") (pin "9") (pintype "passive"))
    )
    (net (code "48") (name "Net-(R37-Pad2)") (class "Default")
      (node (ref "R37") (pin "2") (pintype "passive"))
      (node (ref "U3") (pin "15") (pintype "passive"))
    )
    (net (code "49") (name "Net-(R38-Pad2)") (class "Default")
      (node (ref "R38") (pin "2") (pintype "passive"))
      (node (ref "U3") (pin "13") (pintype "passive"))
    )
    (net (code "50") (name "Net-(R39-Pad2)") (class "Default")
      (node (ref "R39") (pin "2") (pintype "passive"))
      (node (ref "U3") (pin "11") (pintype "passive"))
    )
    (net (code "51") (name "Net-(R40-Pad2)") (class "Default")
      (node (ref "R40") (pin "2") (pintype "passive"))
      (node (ref "U3") (pin "9") (pintype "passive"))
    )
    (net (code "52") (name "Net-(R108-Pad2)") (class "Default")
      (node (ref "R108") (pin "2") (pintype "passive"))
      (node (ref "U2") (pin "15") (pintype "passive"))
    )
    (net (code "53") (name "Net-(R109-Pad2)") (class "Default")
      (node (ref "R109") (pin "2") (pintype "passive"))
      (node (ref "U2") (pin "13") (pintype "passive"))
    )
    (net (code "54") (name "Net-(R110-Pad2)") (class "Default")
      (node (ref "R110") (pin "2") (pintype "passive"))
      (node (ref "U2") (pin "11") (pintype "passive"))
    )
    (net (code "55") (name "Net-(R111-Pad2)") (class "Default")
      (node (ref "R111") (pin "2") (pintype "passive"))
      (node (ref "U2") (pin "9") (pintype "passive"))
    )
    (net (code "56") (name "Net-(R112-Pad1)") (class "Default")
      (node (ref "R112") (pin "1") (pintype "passive"))
      (node (ref "R116") (pin "2") (pintype "passive"))
      (node (ref "U2") (pin "1") (pintype "passive"))
    )
    (net (code "57") (name "Net-(R113-Pad1)") (class "Default")
      (node (ref "R113") (pin "1") (pintype "passive"))
      (node (ref "R117") (pin "2") (pintype "passive"))
      (node (ref "U2") (pin "3") (pintype "passive"))
    )
    (net (code "58") (name "Net-(R114-Pad1)") (class "Default")
      (node (ref "R114") (pin "1") (pintype "passive"))
      (node (ref "R118") (pin "2") (pintype "passive"))
      (node (ref "U2") (pin "5") (pintype "passive"))
    )
    (net (code "59") (name "Net-(R115-Pad1)") (class "Default")
      (node (ref "R115") (pin "1") (pintype "passive"))
      (node (ref "R119") (pin "2") (pintype "passive"))
      (node (ref "U2") (pin "7") (pintype "passive"))
    )
  )
)
